# MCU.net
KiCad netlist of a schematic drawn in Altium Designer
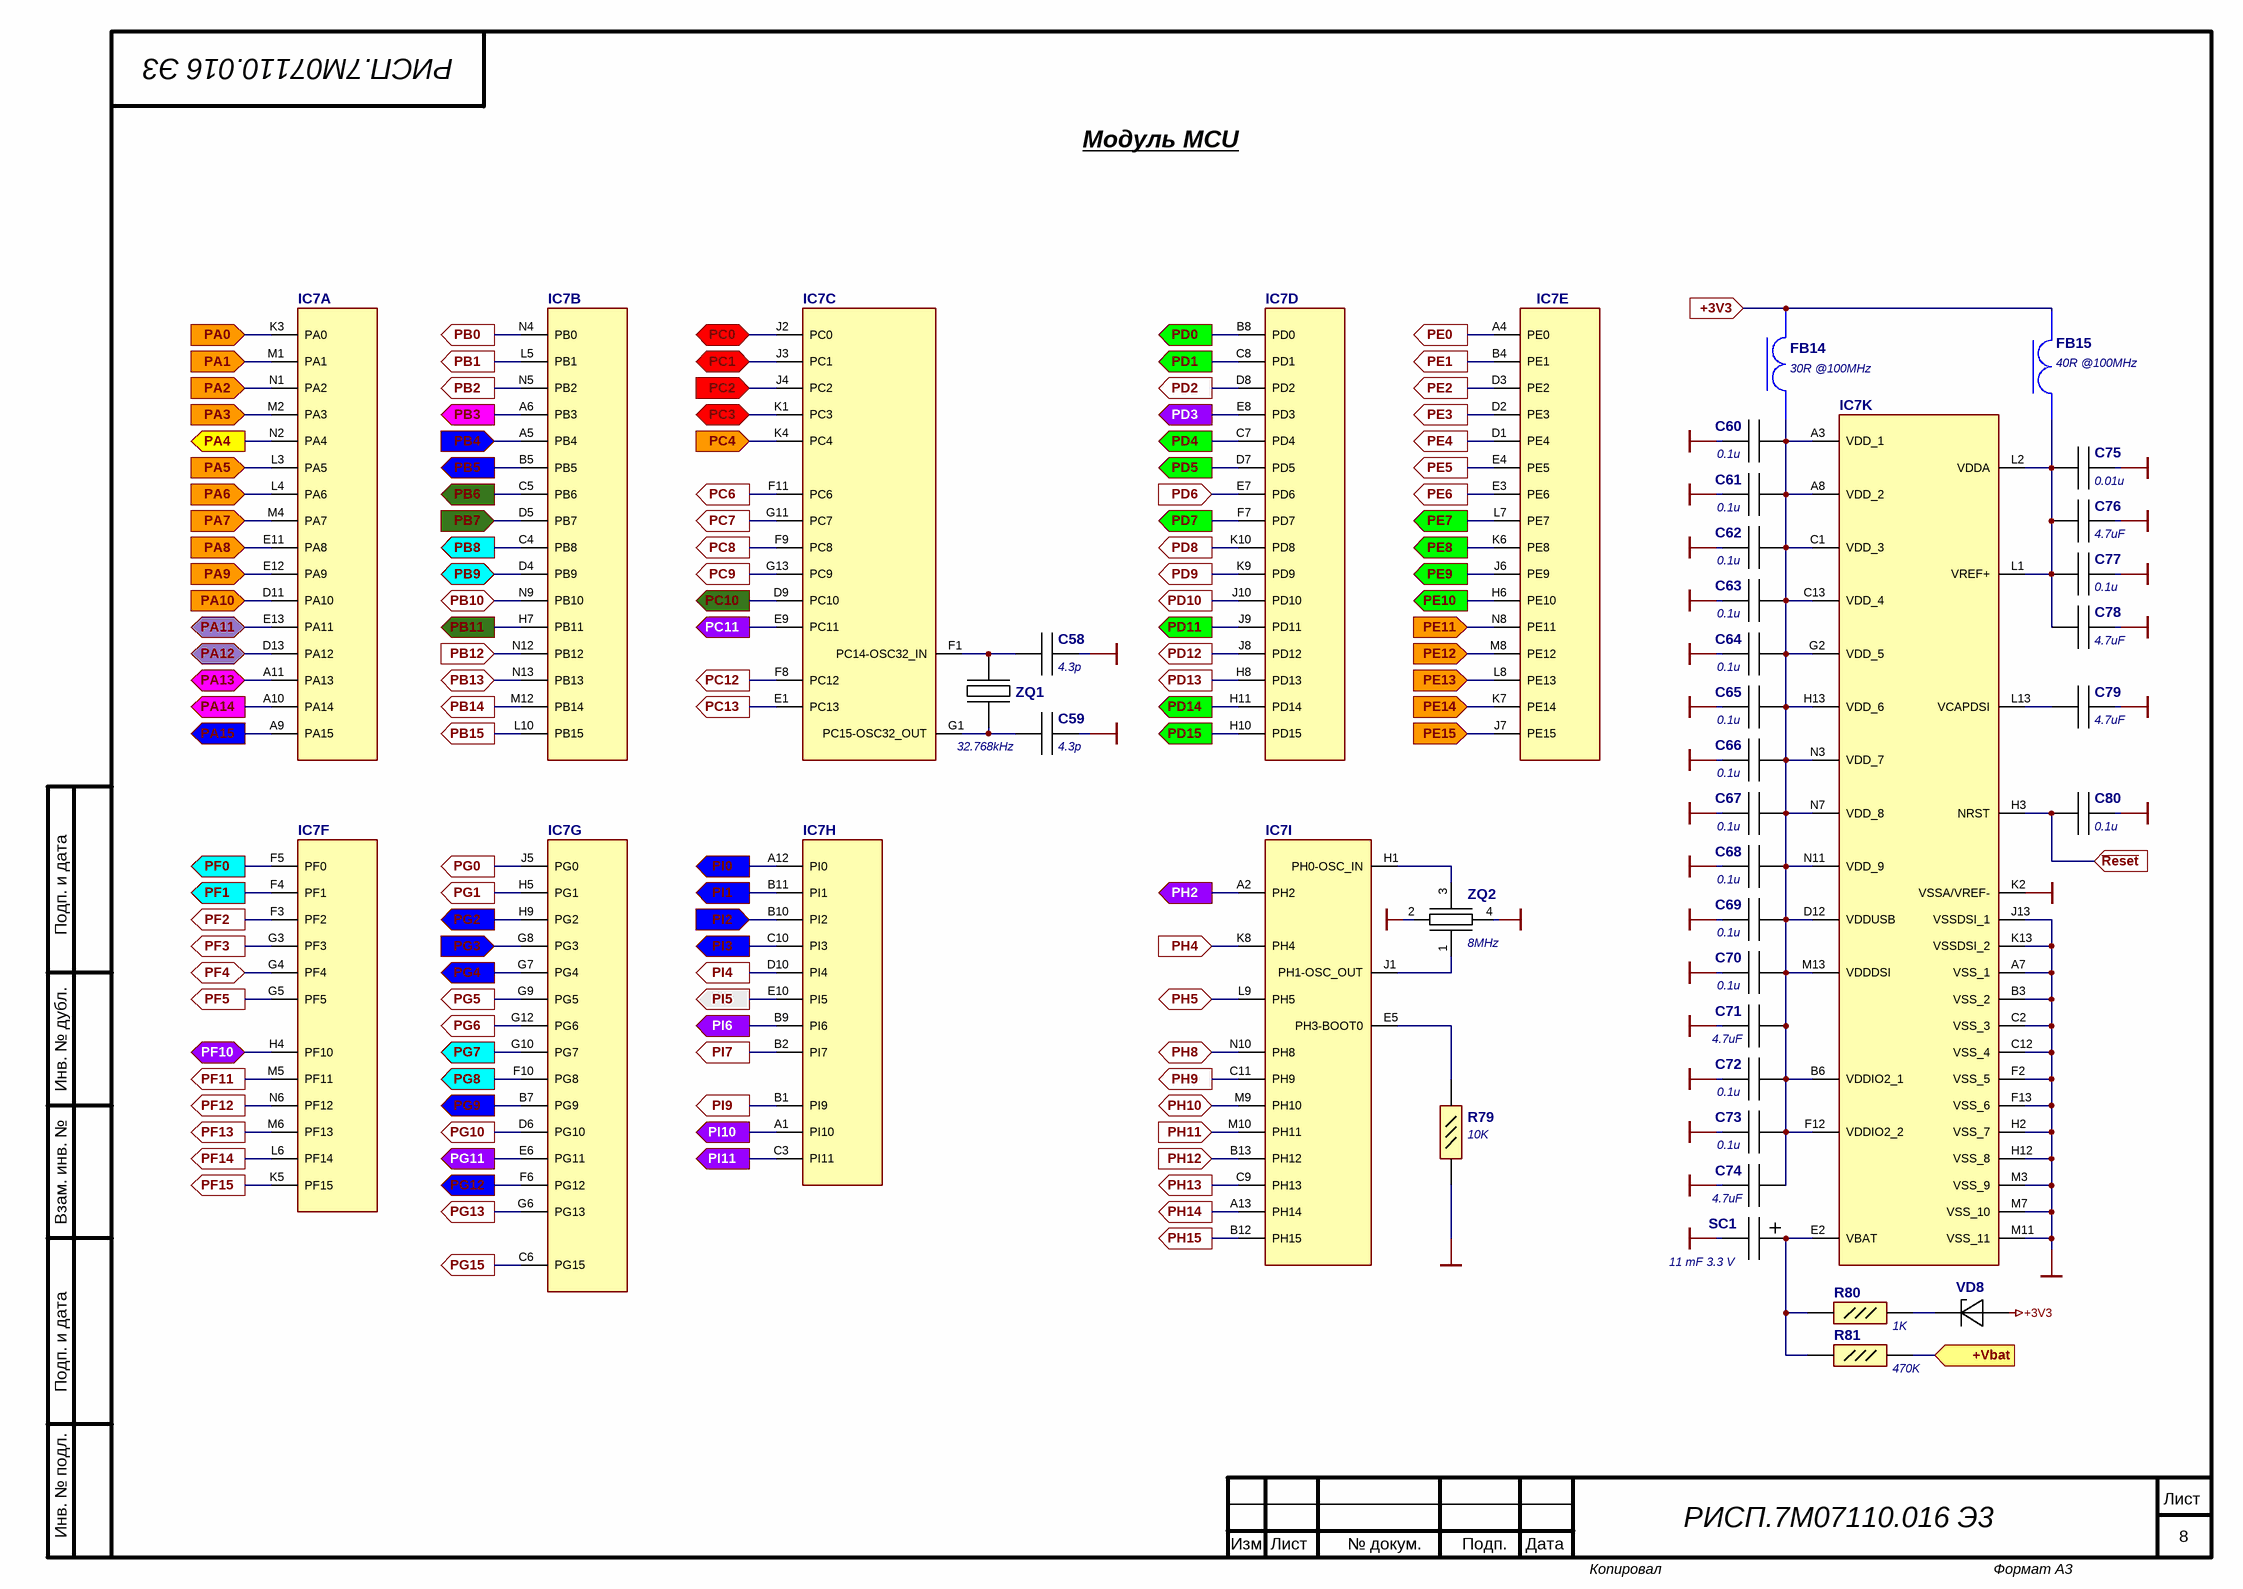
[diagram p0: Модуль MCU.SchDoc]

(export (version "E")
  (design (tool "Eeschema 10.0.6"))
  (components
    (comp (ref "C58")
      (value "4.3p")
      (footprint ":CAP0402 100x50x50")
      (description "CAP CER  50V C0G/NP0 0402")
      (fields (field (name "MANUFACTURER_PART_NUMBER") "GJM1555C1H4R3CB01D"))
      (libsource (lib "Capacitors 0402") (part "GJM1555C1H4R3CB01D"))
    )
    (comp (ref "C59")
      (value "4.3p")
      (footprint ":CAP0402 100x50x50")
      (description "CAP CER  50V C0G/NP0 0402")
      (fields (field (name "MANUFACTURER_PART_NUMBER") "GJM1555C1H4R3CB01D"))
      (libsource (lib "Capacitors 0402") (part "GJM1555C1H4R3CB01D"))
    )
    (comp (ref "C60")
      (value "0.1u")
      (footprint ":CAP0402 100x50x50")
      (description "±10% 25V Ceramic Capacitor X7R 0402 (1005 Metric)")
      (fields
        (field (name "MANUFACTURER_PART_NUMBER") "GRM155R71E104KE14J")
        (field (name "MOUSER PART NUMBER") "81-GRM155R71E104KE4J")
      )
      (libsource (lib "Capacitors 0402") (part "GRM155R71E104KE14J"))
    )
    (comp (ref "C61")
      (value "0.1u")
      (footprint ":CAP0402 100x50x50")
      (description "±10% 25V Ceramic Capacitor X7R 0402 (1005 Metric)")
      (fields
        (field (name "MANUFACTURER_PART_NUMBER") "GRM155R71E104KE14J")
        (field (name "MOUSER PART NUMBER") "81-GRM155R71E104KE4J")
      )
      (libsource (lib "Capacitors 0402") (part "GRM155R71E104KE14J"))
    )
    (comp (ref "C62")
      (value "0.1u")
      (footprint ":CAP0402 100x50x50")
      (description "±10% 25V Ceramic Capacitor X7R 0402 (1005 Metric)")
      (fields
        (field (name "MANUFACTURER_PART_NUMBER") "GRM155R71E104KE14J")
        (field (name "MOUSER PART NUMBER") "81-GRM155R71E104KE4J")
      )
      (libsource (lib "Capacitors 0402") (part "GRM155R71E104KE14J"))
    )
    (comp (ref "C63")
      (value "0.1u")
      (footprint ":CAP0402 100x50x50")
      (description "±10% 25V Ceramic Capacitor X7R 0402 (1005 Metric)")
      (fields
        (field (name "MANUFACTURER_PART_NUMBER") "GRM155R71E104KE14J")
        (field (name "MOUSER PART NUMBER") "81-GRM155R71E104KE4J")
      )
      (libsource (lib "Capacitors 0402") (part "GRM155R71E104KE14J"))
    )
    (comp (ref "C64")
      (value "0.1u")
      (footprint ":CAP0402 100x50x50")
      (description "±10% 25V Ceramic Capacitor X7R 0402 (1005 Metric)")
      (fields
        (field (name "MANUFACTURER_PART_NUMBER") "GRM155R71E104KE14J")
        (field (name "MOUSER PART NUMBER") "81-GRM155R71E104KE4J")
      )
      (libsource (lib "Capacitors 0402") (part "GRM155R71E104KE14J"))
    )
    (comp (ref "C65")
      (value "0.1u")
      (footprint ":CAP0402 100x50x50")
      (description "±10% 25V Ceramic Capacitor X7R 0402 (1005 Metric)")
      (fields
        (field (name "MANUFACTURER_PART_NUMBER") "GRM155R71E104KE14J")
        (field (name "MOUSER PART NUMBER") "81-GRM155R71E104KE4J")
      )
      (libsource (lib "Capacitors 0402") (part "GRM155R71E104KE14J"))
    )
    (comp (ref "C66")
      (value "0.1u")
      (footprint ":CAP0402 100x50x50")
      (description "±10% 25V Ceramic Capacitor X7R 0402 (1005 Metric)")
      (fields
        (field (name "MANUFACTURER_PART_NUMBER") "GRM155R71E104KE14J")
        (field (name "MOUSER PART NUMBER") "81-GRM155R71E104KE4J")
      )
      (libsource (lib "Capacitors 0402") (part "GRM155R71E104KE14J"))
    )
    (comp (ref "C67")
      (value "0.1u")
      (footprint ":CAP0402 100x50x50")
      (description "±10% 25V Ceramic Capacitor X7R 0402 (1005 Metric)")
      (fields
        (field (name "MANUFACTURER_PART_NUMBER") "GRM155R71E104KE14J")
        (field (name "MOUSER PART NUMBER") "81-GRM155R71E104KE4J")
      )
      (libsource (lib "Capacitors 0402") (part "GRM155R71E104KE14J"))
    )
    (comp (ref "C68")
      (value "0.1u")
      (footprint ":CAP0402 100x50x50")
      (description "±10% 25V Ceramic Capacitor X7R 0402 (1005 Metric)")
      (fields
        (field (name "MANUFACTURER_PART_NUMBER") "GRM155R71E104KE14J")
        (field (name "MOUSER PART NUMBER") "81-GRM155R71E104KE4J")
      )
      (libsource (lib "Capacitors 0402") (part "GRM155R71E104KE14J"))
    )
    (comp (ref "C69")
      (value "0.1u")
      (footprint ":CAP0402 100x50x50")
      (description "±10% 25V Ceramic Capacitor X7R 0402 (1005 Metric)")
      (fields
        (field (name "MANUFACTURER_PART_NUMBER") "GRM155R71E104KE14J")
        (field (name "MOUSER PART NUMBER") "81-GRM155R71E104KE4J")
      )
      (libsource (lib "Capacitors 0402") (part "GRM155R71E104KE14J"))
    )
    (comp (ref "C70")
      (value "0.1u")
      (footprint ":CAP0402 100x50x50")
      (description "±10% 25V Ceramic Capacitor X7R 0402 (1005 Metric)")
      (fields
        (field (name "MANUFACTURER_PART_NUMBER") "GRM155R71E104KE14J")
        (field (name "MOUSER PART NUMBER") "81-GRM155R71E104KE4J")
      )
      (libsource (lib "Capacitors 0402") (part "GRM155R71E104KE14J"))
    )
    (comp (ref "C71")
      (value "4.7uF")
      (footprint ":CAP0805 C2012X125")
      (description "CAP CER 4.7uF 25V X7R 0805")
      (fields (field (name "MANUFACTURER_PART_NUMBER") "GRM21BZ71E475KE15L"))
      (libsource (lib "Capacitors 0805") (part "GRM21BZ71E475KE15L"))
    )
    (comp (ref "C72")
      (value "0.1u")
      (footprint ":CAP0402 100x50x50")
      (description "±10% 25V Ceramic Capacitor X7R 0402 (1005 Metric)")
      (fields
        (field (name "MANUFACTURER_PART_NUMBER") "GRM155R71E104KE14J")
        (field (name "MOUSER PART NUMBER") "81-GRM155R71E104KE4J")
      )
      (libsource (lib "Capacitors 0402") (part "GRM155R71E104KE14J"))
    )
    (comp (ref "C73")
      (value "0.1u")
      (footprint ":CAP0402 100x50x50")
      (description "±10% 25V Ceramic Capacitor X7R 0402 (1005 Metric)")
      (fields
        (field (name "MANUFACTURER_PART_NUMBER") "GRM155R71E104KE14J")
        (field (name "MOUSER PART NUMBER") "81-GRM155R71E104KE4J")
      )
      (libsource (lib "Capacitors 0402") (part "GRM155R71E104KE14J"))
    )
    (comp (ref "C74")
      (value "4.7uF")
      (footprint ":CAP0805 C2012X125")
      (description "CAP CER 4.7uF 25V X7R 0805")
      (fields (field (name "MANUFACTURER_PART_NUMBER") "GRM21BZ71E475KE15L"))
      (libsource (lib "Capacitors 0805") (part "GRM21BZ71E475KE15L"))
    )
    (comp (ref "C75")
      (value "0.01u")
      (footprint ":CAP0402 100x50x50")
      (description "±5% 35V Ceramic Capacitor C0G, NP0 0402 (1005 Metric)")
      (fields (field (name "MANUFACTURER_PART_NUMBER") "GRM1555CYA103JE01D"))
      (libsource (lib "Capacitors 0402") (part "GRM1555CYA103JE01D"))
    )
    (comp (ref "C76")
      (value "4.7uF")
      (footprint ":CAP0805 C2012X125")
      (description "CAP CER 4.7uF 25V X7R 0805")
      (fields (field (name "MANUFACTURER_PART_NUMBER") "GRM21BZ71E475KE15L"))
      (libsource (lib "Capacitors 0805") (part "GRM21BZ71E475KE15L"))
    )
    (comp (ref "C77")
      (value "0.1u")
      (footprint ":CAP0402 100x50x50")
      (description "±10% 25V Ceramic Capacitor X7R 0402 (1005 Metric)")
      (fields
        (field (name "MANUFACTURER_PART_NUMBER") "GRM155R71E104KE14J")
        (field (name "MOUSER PART NUMBER") "81-GRM155R71E104KE4J")
      )
      (libsource (lib "Capacitors 0402") (part "GRM155R71E104KE14J"))
    )
    (comp (ref "C78")
      (value "4.7uF")
      (footprint ":CAP0805 C2012X125")
      (description "CAP CER 4.7uF 25V X7R 0805")
      (fields (field (name "MANUFACTURER_PART_NUMBER") "GRM21BZ71E475KE15L"))
      (libsource (lib "Capacitors 0805") (part "GRM21BZ71E475KE15L"))
    )
    (comp (ref "C79")
      (value "4.7uF")
      (footprint ":CAP0805 C2012X125")
      (description "CAP CER 4.7uF 25V X7R 0805")
      (fields (field (name "MANUFACTURER_PART_NUMBER") "GRM21BZ71E475KE15L"))
      (libsource (lib "Capacitors 0805") (part "GRM21BZ71E475KE15L"))
    )
    (comp (ref "C80")
      (value "0.1u")
      (footprint ":CAP0402 100x50x50")
      (description "±10% 25V Ceramic Capacitor X7R 0402 (1005 Metric)")
      (fields
        (field (name "MANUFACTURER_PART_NUMBER") "GRM155R71E104KE14J")
        (field (name "MOUSER PART NUMBER") "81-GRM155R71E104KE4J")
      )
      (libsource (lib "Capacitors 0402") (part "GRM155R71E104KE14J"))
    )
    (comp (ref "FB14")
      (value "30R @100MHz")
      (footprint ":FER BLM18SP300SN1D")
      (description "30 Ohms @ 100MHz 1 Power Line Ferrite Bead 0603 (1608 Metric) 6A 8mOhm")
      (fields
        (field (name "MANUFACTURER_PART_NUMBER") "BLM18SP300SN1D")
        (field (name "MOUSER PART NUMBER") "81-BLM18SP300SN1D")
      )
      (libsource (lib "Ferrite Bead") (part "BLM18SP300SN1D"))
    )
    (comp (ref "FB15")
      (value "40R @100MHz")
      (footprint ":FER MMZ1005Y400CTD25")
      (description "40 Ohms @ 100MHz 1 Signal Line Ferrite Bead 0402 (1005 Metric) 550mA 100mOhm")
      (fields
        (field (name "MANUFACTURER_PART_NUMBER") "MMZ1005Y400CTD25")
        (field (name "MOUSER PART NUMBER") "810-MMZ1005Y400CTD25")
      )
      (libsource (lib "Ferrite Bead") (part "MMZ1005Y400CTD25"))
    )
    (comp (ref "IC7")
      (value "STM32L4S9AII6")
      (footprint ":BGA169 P700X700X60")
      (description "MCU 32BIT 2MB FLASH")
      (fields (field (name "MOUSER PART NUMBER") "511-STM32L4S9AII6"))
      (libsource (lib "Digital ICs") (part "STM32L4S9AII6"))
    )
    (comp (ref "R79")
      (value "RC0402FR-07")
      (footprint ":RES0402")
      (fields (field (name "MANUFACTURER_PART_NUMBER (PART 2: VALUE)") "10K"))
      (libsource (lib "Resistors 0402") (part "RC0402FR-07"))
    )
    (comp (ref "R80")
      (value "RC0402FR-07")
      (footprint ":RES0402")
      (fields (field (name "MANUFACTURER_PART_NUMBER (PART 2: VALUE)") "1K"))
      (libsource (lib "") (part "RC0402FR-07_1"))
    )
    (comp (ref "R81")
      (value "RC0402FR-07")
      (footprint ":RES0402")
      (fields (field (name "MANUFACTURER_PART_NUMBER (PART 2: VALUE)") "470K"))
      (libsource (lib "") (part "RC0402FR-07_1"))
    )
    (comp (ref "SC1")
      (value "11 mF 3.3 V")
      (footprint ":CAP CPH3225A")
      (description "11 mF (EDLC) Supercapacitor 3.3 V 1210 (3225 Metric)")
      (fields
        (field (name "MANUFACTURER_PART_NUMBER") "CPH3225A")
        (field (name "MOUSER PART NUMBER") "628-CPH3225A")
      )
      (libsource (lib "Super Capacitors") (part "CPH3225A"))
    )
    (comp (ref "VD8")
      (value "30V 0.1A")
      (footprint ":DIODE SOD-923F")
      (description "Diodes Schottky 0402 30V 0.1A")
      (fields
        (field (name "MANUFACTURER_PART_NUMBER") "CDBQR0130R")
        (field (name "MOUSER PART NUMBER") "750-CDBQR0130R")
      )
      (libsource (lib "Diodes 0402") (part "CDBQR0130R"))
    )
    (comp (ref "ZQ1")
      (value "32.768kHz")
      (footprint ":RESO 12.87181")
      (description "CRYSTAL 32.7680KHZ\r\n±20ppm Crystal 12.5pF 2-SMD\r\nESR: 70 kOhms")
      (fields (field (name "MANUFACTURER_PART_NUMBER") "12.87181"))
      (libsource (lib "Crystal and TXCO") (part "12.87181"))
    )
    (comp (ref "ZQ2")
      (value "8MHz")
      (footprint ":RESO LFXTAL069277REEL")
      (description "CRYSTAL 8MHz\r\n±20ppm Crystal 20pF 4-SMD\r\nESR: 150 Ohms")
      (fields (field (name "MANUFACTURER_PART_NUMBER") "LFXTAL069277REEL"))
      (libsource (lib "Crystal and TXCO") (part "LFXTAL069277REEL"))
    )
  )
  (nets
    (net (code "1") (name "+3V3") (class "Default")
      (node (ref "FB14") (pin "2") (pinfunction "2_2") (pintype "passive"))
      (node (ref "FB15") (pin "1") (pinfunction "1_1") (pintype "passive"))
      (node (ref "VD8") (pin "2") (pinfunction "A_2") (pintype "passive"))
    )
    (net (code "2") (name "/+Vbat") (class "Default")
      (node (ref "R81") (pin "1") (pinfunction "1_1") (pintype "passive"))
    )
    (net (code "3") (name "/PA0") (class "Default")
      (node (ref "IC7") (pin "K3") (pinfunction "PA0_K3") (pintype "passive"))
    )
    (net (code "4") (name "/PA1") (class "Default")
      (node (ref "IC7") (pin "M1") (pinfunction "PA1_M1") (pintype "passive"))
    )
    (net (code "5") (name "/PA2") (class "Default")
      (node (ref "IC7") (pin "N1") (pinfunction "PA2_N1") (pintype "passive"))
    )
    (net (code "6") (name "/PA3") (class "Default")
      (node (ref "IC7") (pin "M2") (pinfunction "PA3_M2") (pintype "passive"))
    )
    (net (code "7") (name "/PA4") (class "Default")
      (node (ref "IC7") (pin "N2") (pinfunction "PA4_N2") (pintype "passive"))
    )
    (net (code "8") (name "/PA5") (class "Default")
      (node (ref "IC7") (pin "L3") (pinfunction "PA5_L3") (pintype "passive"))
    )
    (net (code "9") (name "/PA6") (class "Default")
      (node (ref "IC7") (pin "L4") (pinfunction "PA6_L4") (pintype "passive"))
    )
    (net (code "10") (name "/PA7") (class "Default")
      (node (ref "IC7") (pin "M4") (pinfunction "PA7_M4") (pintype "passive"))
    )
    (net (code "11") (name "/PA8") (class "Default")
      (node (ref "IC7") (pin "E11") (pinfunction "PA8_E11") (pintype "passive"))
    )
    (net (code "12") (name "/PA9") (class "Default")
      (node (ref "IC7") (pin "E12") (pinfunction "PA9_E12") (pintype "passive"))
    )
    (net (code "13") (name "/PA10") (class "Default")
      (node (ref "IC7") (pin "D11") (pinfunction "PA10_D11") (pintype "passive"))
    )
    (net (code "14") (name "/PA11") (class "Default")
      (node (ref "IC7") (pin "E13") (pinfunction "PA11_E13") (pintype "passive"))
    )
    (net (code "15") (name "/PA12") (class "Default")
      (node (ref "IC7") (pin "D13") (pinfunction "PA12_D13") (pintype "passive"))
    )
    (net (code "16") (name "/PA13") (class "Default")
      (node (ref "IC7") (pin "A11") (pinfunction "PA13_A11") (pintype "passive"))
    )
    (net (code "17") (name "/PA14") (class "Default")
      (node (ref "IC7") (pin "A10") (pinfunction "PA14_A10") (pintype "passive"))
    )
    (net (code "18") (name "/PA15") (class "Default")
      (node (ref "IC7") (pin "A9") (pinfunction "PA15_A9") (pintype "passive"))
    )
    (net (code "19") (name "/PB0") (class "Default")
      (node (ref "IC7") (pin "N4") (pinfunction "PB0_N4") (pintype "passive"))
    )
    (net (code "20") (name "/PB1") (class "Default")
      (node (ref "IC7") (pin "L5") (pinfunction "PB1_L5") (pintype "passive"))
    )
    (net (code "21") (name "/PB2") (class "Default")
      (node (ref "IC7") (pin "N5") (pinfunction "PB2_N5") (pintype "passive"))
    )
    (net (code "22") (name "/PB3") (class "Default")
      (node (ref "IC7") (pin "A6") (pinfunction "PB3_A6") (pintype "passive"))
    )
    (net (code "23") (name "/PB4") (class "Default")
      (node (ref "IC7") (pin "A5") (pinfunction "PB4_A5") (pintype "passive"))
    )
    (net (code "24") (name "/PB5") (class "Default")
      (node (ref "IC7") (pin "B5") (pinfunction "PB5_B5") (pintype "passive"))
    )
    (net (code "25") (name "/PB6") (class "Default")
      (node (ref "IC7") (pin "C5") (pinfunction "PB6_C5") (pintype "passive"))
    )
    (net (code "26") (name "/PB7") (class "Default")
      (node (ref "IC7") (pin "D5") (pinfunction "PB7_D5") (pintype "passive"))
    )
    (net (code "27") (name "/PB8") (class "Default")
      (node (ref "IC7") (pin "C4") (pinfunction "PB8_C4") (pintype "passive"))
    )
    (net (code "28") (name "/PB9") (class "Default")
      (node (ref "IC7") (pin "D4") (pinfunction "PB9_D4") (pintype "passive"))
    )
    (net (code "29") (name "/PB10") (class "Default")
      (node (ref "IC7") (pin "N9") (pinfunction "PB10_N9") (pintype "passive"))
    )
    (net (code "30") (name "/PB11") (class "Default")
      (node (ref "IC7") (pin "H7") (pinfunction "PB11_H7") (pintype "passive"))
    )
    (net (code "31") (name "/PB12") (class "Default")
      (node (ref "IC7") (pin "N12") (pinfunction "PB12_N12") (pintype "passive"))
    )
    (net (code "32") (name "/PB13") (class "Default")
      (node (ref "IC7") (pin "N13") (pinfunction "PB13_N13") (pintype "passive"))
    )
    (net (code "33") (name "/PB14") (class "Default")
      (node (ref "IC7") (pin "M12") (pinfunction "PB14_M12") (pintype "passive"))
    )
    (net (code "34") (name "/PB15") (class "Default")
      (node (ref "IC7") (pin "L10") (pinfunction "PB15_L10") (pintype "passive"))
    )
    (net (code "35") (name "/PC0") (class "Default")
      (node (ref "IC7") (pin "J2") (pinfunction "PC0_J2") (pintype "passive"))
    )
    (net (code "36") (name "/PC1") (class "Default")
      (node (ref "IC7") (pin "J3") (pinfunction "PC1_J3") (pintype "passive"))
    )
    (net (code "37") (name "/PC2") (class "Default")
      (node (ref "IC7") (pin "J4") (pinfunction "PC2_J4") (pintype "passive"))
    )
    (net (code "38") (name "/PC3") (class "Default")
      (node (ref "IC7") (pin "K1") (pinfunction "PC3_K1") (pintype "passive"))
    )
    (net (code "39") (name "/PC4") (class "Default")
      (node (ref "IC7") (pin "K4") (pinfunction "PC4_K4") (pintype "passive"))
    )
    (net (code "40") (name "/PC6") (class "Default")
      (node (ref "IC7") (pin "F11") (pinfunction "PC6_F11") (pintype "passive"))
    )
    (net (code "41") (name "/PC7") (class "Default")
      (node (ref "IC7") (pin "G11") (pinfunction "PC7_G11") (pintype "passive"))
    )
    (net (code "42") (name "/PC8") (class "Default")
      (node (ref "IC7") (pin "F9") (pinfunction "PC8_F9") (pintype "passive"))
    )
    (net (code "43") (name "/PC9") (class "Default")
      (node (ref "IC7") (pin "G13") (pinfunction "PC9_G13") (pintype "passive"))
    )
    (net (code "44") (name "/PC10") (class "Default")
      (node (ref "IC7") (pin "D9") (pinfunction "PC10_D9") (pintype "passive"))
    )
    (net (code "45") (name "/PC11") (class "Default")
      (node (ref "IC7") (pin "E9") (pinfunction "PC11_E9") (pintype "passive"))
    )
    (net (code "46") (name "/PC12") (class "Default")
      (node (ref "IC7") (pin "F8") (pinfunction "PC12_F8") (pintype "passive"))
    )
    (net (code "47") (name "/PC13") (class "Default")
      (node (ref "IC7") (pin "E1") (pinfunction "PC13_E1") (pintype "passive"))
    )
    (net (code "48") (name "/PD0") (class "Default")
      (node (ref "IC7") (pin "B8") (pinfunction "PD0_B8") (pintype "passive"))
    )
    (net (code "49") (name "/PD1") (class "Default")
      (node (ref "IC7") (pin "C8") (pinfunction "PD1_C8") (pintype "passive"))
    )
    (net (code "50") (name "/PD2") (class "Default")
      (node (ref "IC7") (pin "D8") (pinfunction "PD2_D8") (pintype "passive"))
    )
    (net (code "51") (name "/PD3") (class "Default")
      (node (ref "IC7") (pin "E8") (pinfunction "PD3_E8") (pintype "passive"))
    )
    (net (code "52") (name "/PD4") (class "Default")
      (node (ref "IC7") (pin "C7") (pinfunction "PD4_C7") (pintype "passive"))
    )
    (net (code "53") (name "/PD5") (class "Default")
      (node (ref "IC7") (pin "D7") (pinfunction "PD5_D7") (pintype "passive"))
    )
    (net (code "54") (name "/PD6") (class "Default")
      (node (ref "IC7") (pin "E7") (pinfunction "PD6_E7") (pintype "passive"))
    )
    (net (code "55") (name "/PD7") (class "Default")
      (node (ref "IC7") (pin "F7") (pinfunction "PD7_F7") (pintype "passive"))
    )
    (net (code "56") (name "/PD8") (class "Default")
      (node (ref "IC7") (pin "K10") (pinfunction "PD8_K10") (pintype "passive"))
    )
    (net (code "57") (name "/PD9") (class "Default")
      (node (ref "IC7") (pin "K9") (pinfunction "PD9_K9") (pintype "passive"))
    )
    (net (code "58") (name "/PD10") (class "Default")
      (node (ref "IC7") (pin "J10") (pinfunction "PD10_J10") (pintype "passive"))
    )
    (net (code "59") (name "/PD11") (class "Default")
      (node (ref "IC7") (pin "J9") (pinfunction "PD11_J9") (pintype "passive"))
    )
    (net (code "60") (name "/PD12") (class "Default")
      (node (ref "IC7") (pin "J8") (pinfunction "PD12_J8") (pintype "passive"))
    )
    (net (code "61") (name "/PD13") (class "Default")
      (node (ref "IC7") (pin "H8") (pinfunction "PD13_H8") (pintype "passive"))
    )
    (net (code "62") (name "/PD14") (class "Default")
      (node (ref "IC7") (pin "H11") (pinfunction "PD14_H11") (pintype "passive"))
    )
    (net (code "63") (name "/PD15") (class "Default")
      (node (ref "IC7") (pin "H10") (pinfunction "PD15_H10") (pintype "passive"))
    )
    (net (code "64") (name "/PE0") (class "Default")
      (node (ref "IC7") (pin "A4") (pinfunction "PE0_A4") (pintype "passive"))
    )
    (net (code "65") (name "/PE1") (class "Default")
      (node (ref "IC7") (pin "B4") (pinfunction "PE1_B4") (pintype "passive"))
    )
    (net (code "66") (name "/PE2") (class "Default")
      (node (ref "IC7") (pin "D3") (pinfunction "PE2_D3") (pintype "passive"))
    )
    (net (code "67") (name "/PE3") (class "Default")
      (node (ref "IC7") (pin "D2") (pinfunction "PE3_D2") (pintype "passive"))
    )
    (net (code "68") (name "/PE4") (class "Default")
      (node (ref "IC7") (pin "D1") (pinfunction "PE4_D1") (pintype "passive"))
    )
    (net (code "69") (name "/PE5") (class "Default")
      (node (ref "IC7") (pin "E4") (pinfunction "PE5_E4") (pintype "passive"))
    )
    (net (code "70") (name "/PE6") (class "Default")
      (node (ref "IC7") (pin "E3") (pinfunction "PE6_E3") (pintype "passive"))
    )
    (net (code "71") (name "/PE7") (class "Default")
      (node (ref "IC7") (pin "L7") (pinfunction "PE7_L7") (pintype "passive"))
    )
    (net (code "72") (name "/PE8") (class "Default")
      (node (ref "IC7") (pin "K6") (pinfunction "PE8_K6") (pintype "passive"))
    )
    (net (code "73") (name "/PE9") (class "Default")
      (node (ref "IC7") (pin "J6") (pinfunction "PE9_J6") (pintype "passive"))
    )
    (net (code "74") (name "/PE10") (class "Default")
      (node (ref "IC7") (pin "H6") (pinfunction "PE10_H6") (pintype "passive"))
    )
    (net (code "75") (name "/PE11") (class "Default")
      (node (ref "IC7") (pin "N8") (pinfunction "PE11_N8") (pintype "passive"))
    )
    (net (code "76") (name "/PE12") (class "Default")
      (node (ref "IC7") (pin "M8") (pinfunction "PE12_M8") (pintype "passive"))
    )
    (net (code "77") (name "/PE13") (class "Default")
      (node (ref "IC7") (pin "L8") (pinfunction "PE13_L8") (pintype "passive"))
    )
    (net (code "78") (name "/PE14") (class "Default")
      (node (ref "IC7") (pin "K7") (pinfunction "PE14_K7") (pintype "passive"))
    )
    (net (code "79") (name "/PE15") (class "Default")
      (node (ref "IC7") (pin "J7") (pinfunction "PE15_J7") (pintype "passive"))
    )
    (net (code "80") (name "/PF0") (class "Default")
      (node (ref "IC7") (pin "F5") (pinfunction "PF0_F5") (pintype "passive"))
    )
    (net (code "81") (name "/PF1") (class "Default")
      (node (ref "IC7") (pin "F4") (pinfunction "PF1_F4") (pintype "passive"))
    )
    (net (code "82") (name "/PF2") (class "Default")
      (node (ref "IC7") (pin "F3") (pinfunction "PF2_F3") (pintype "passive"))
    )
    (net (code "83") (name "/PF3") (class "Default")
      (node (ref "IC7") (pin "G3") (pinfunction "PF3_G3") (pintype "passive"))
    )
    (net (code "84") (name "/PF4") (class "Default")
      (node (ref "IC7") (pin "G4") (pinfunction "PF4_G4") (pintype "passive"))
    )
    (net (code "85") (name "/PF5") (class "Default")
      (node (ref "IC7") (pin "G5") (pinfunction "PF5_G5") (pintype "passive"))
    )
    (net (code "86") (name "/PF10") (class "Default")
      (node (ref "IC7") (pin "H4") (pinfunction "PF10_H4") (pintype "passive"))
    )
    (net (code "87") (name "/PF11") (class "Default")
      (node (ref "IC7") (pin "M5") (pinfunction "PF11_M5") (pintype "passive"))
    )
    (net (code "88") (name "/PF12") (class "Default")
      (node (ref "IC7") (pin "N6") (pinfunction "PF12_N6") (pintype "passive"))
    )
    (net (code "89") (name "/PF13") (class "Default")
      (node (ref "IC7") (pin "M6") (pinfunction "PF13_M6") (pintype "passive"))
    )
    (net (code "90") (name "/PF14") (class "Default")
      (node (ref "IC7") (pin "L6") (pinfunction "PF14_L6") (pintype "passive"))
    )
    (net (code "91") (name "/PF15") (class "Default")
      (node (ref "IC7") (pin "K5") (pinfunction "PF15_K5") (pintype "passive"))
    )
    (net (code "92") (name "/PG0") (class "Default")
      (node (ref "IC7") (pin "J5") (pinfunction "PG0_J5") (pintype "passive"))
    )
    (net (code "93") (name "/PG1") (class "Default")
      (node (ref "IC7") (pin "H5") (pinfunction "PG1_H5") (pintype "passive"))
    )
    (net (code "94") (name "/PG2") (class "Default")
      (node (ref "IC7") (pin "H9") (pinfunction "PG2_H9") (pintype "passive"))
    )
    (net (code "95") (name "/PG3") (class "Default")
      (node (ref "IC7") (pin "G8") (pinfunction "PG3_G8") (pintype "passive"))
    )
    (net (code "96") (name "/PG4") (class "Default")
      (node (ref "IC7") (pin "G7") (pinfunction "PG4_G7") (pintype "passive"))
    )
    (net (code "97") (name "/PG5") (class "Default")
      (node (ref "IC7") (pin "G9") (pinfunction "PG5_G9") (pintype "passive"))
    )
    (net (code "98") (name "/PG6") (class "Default")
      (node (ref "IC7") (pin "G12") (pinfunction "PG6_G12") (pintype "passive"))
    )
    (net (code "99") (name "/PG7") (class "Default")
      (node (ref "IC7") (pin "G10") (pinfunction "PG7_G10") (pintype "passive"))
    )
    (net (code "100") (name "/PG8") (class "Default")
      (node (ref "IC7") (pin "F10") (pinfunction "PG8_F10") (pintype "passive"))
    )
    (net (code "101") (name "/PG9") (class "Default")
      (node (ref "IC7") (pin "B7") (pinfunction "PG9_B7") (pintype "passive"))
    )
    (net (code "102") (name "/PG10") (class "Default")
      (node (ref "IC7") (pin "D6") (pinfunction "PG10_D6") (pintype "passive"))
    )
    (net (code "103") (name "/PG11") (class "Default")
      (node (ref "IC7") (pin "E6") (pinfunction "PG11_E6") (pintype "passive"))
    )
    (net (code "104") (name "/PG12") (class "Default")
      (node (ref "IC7") (pin "F6") (pinfunction "PG12_F6") (pintype "passive"))
    )
    (net (code "105") (name "/PG13") (class "Default")
      (node (ref "IC7") (pin "G6") (pinfunction "PG13_G6") (pintype "passive"))
    )
    (net (code "106") (name "/PG15") (class "Default")
      (node (ref "IC7") (pin "C6") (pinfunction "PG15_C6") (pintype "passive"))
    )
    (net (code "107") (name "/PH2") (class "Default")
      (node (ref "IC7") (pin "A2") (pinfunction "PH2_A2") (pintype "passive"))
    )
    (net (code "108") (name "/PH4") (class "Default")
      (node (ref "IC7") (pin "K8") (pinfunction "PH4_K8") (pintype "passive"))
    )
    (net (code "109") (name "/PH5") (class "Default")
      (node (ref "IC7") (pin "L9") (pinfunction "PH5_L9") (pintype "passive"))
    )
    (net (code "110") (name "/PH8") (class "Default")
      (node (ref "IC7") (pin "N10") (pinfunction "PH8_N10") (pintype "passive"))
    )
    (net (code "111") (name "/PH9") (class "Default")
      (node (ref "IC7") (pin "C11") (pinfunction "PH9_C11") (pintype "passive"))
    )
    (net (code "112") (name "/PH10") (class "Default")
      (node (ref "IC7") (pin "M9") (pinfunction "PH10_M9") (pintype "passive"))
    )
    (net (code "113") (name "/PH11") (class "Default")
      (node (ref "IC7") (pin "M10") (pinfunction "PH11_M10") (pintype "passive"))
    )
    (net (code "114") (name "/PH12") (class "Default")
      (node (ref "IC7") (pin "B13") (pinfunction "PH12_B13") (pintype "passive"))
    )
    (net (code "115") (name "/PH13") (class "Default")
      (node (ref "IC7") (pin "C9") (pinfunction "PH13_C9") (pintype "passive"))
    )
    (net (code "116") (name "/PH14") (class "Default")
      (node (ref "IC7") (pin "A13") (pinfunction "PH14_A13") (pintype "passive"))
    )
    (net (code "117") (name "/PH15") (class "Default")
      (node (ref "IC7") (pin "B12") (pinfunction "PH15_B12") (pintype "passive"))
    )
    (net (code "118") (name "/PI0") (class "Default")
      (node (ref "IC7") (pin "A12") (pinfunction "PI0_A12") (pintype "passive"))
    )
    (net (code "119") (name "/PI1") (class "Default")
      (node (ref "IC7") (pin "B11") (pinfunction "PI1_B11") (pintype "passive"))
    )
    (net (code "120") (name "/PI2") (class "Default")
      (node (ref "IC7") (pin "B10") (pinfunction "PI2_B10") (pintype "passive"))
    )
    (net (code "121") (name "/PI3") (class "Default")
      (node (ref "IC7") (pin "C10") (pinfunction "PI3_C10") (pintype "passive"))
    )
    (net (code "122") (name "/PI4") (class "Default")
      (node (ref "IC7") (pin "D10") (pinfunction "PI4_D10") (pintype "passive"))
    )
    (net (code "123") (name "/PI5") (class "Default")
      (node (ref "IC7") (pin "E10") (pinfunction "PI5_E10") (pintype "passive"))
    )
    (net (code "124") (name "/PI6") (class "Default")
      (node (ref "IC7") (pin "B9") (pinfunction "PI6_B9") (pintype "passive"))
    )
    (net (code "125") (name "/PI7") (class "Default")
      (node (ref "IC7") (pin "B2") (pinfunction "PI7_B2") (pintype "passive"))
    )
    (net (code "126") (name "/PI9") (class "Default")
      (node (ref "IC7") (pin "B1") (pinfunction "PI9_B1") (pintype "passive"))
    )
    (net (code "127") (name "/PI10") (class "Default")
      (node (ref "IC7") (pin "A1") (pinfunction "PI10_A1") (pintype "passive"))
    )
    (net (code "128") (name "/PI11") (class "Default")
      (node (ref "IC7") (pin "C3") (pinfunction "PI11_C3") (pintype "passive"))
    )
    (net (code "129") (name "/~{Reset}") (class "Default")
      (node (ref "C80") (pin "1") (pinfunction "1_1") (pintype "passive"))
      (node (ref "IC7") (pin "H3") (pinfunction "NRST_H3") (pintype "passive"))
    )
    (net (code "130") (name "GND") (class "Default")
      (node (ref "C58") (pin "2") (pinfunction "2_2") (pintype "passive"))
      (node (ref "C59") (pin "2") (pinfunction "2_2") (pintype "passive"))
      (node (ref "C60") (pin "1") (pinfunction "1_1") (pintype "passive"))
      (node (ref "C61") (pin "1") (pinfunction "1_1") (pintype "passive"))
      (node (ref "C62") (pin "1") (pinfunction "1_1") (pintype "passive"))
      (node (ref "C63") (pin "1") (pinfunction "1_1") (pintype "passive"))
      (node (ref "C64") (pin "1") (pinfunction "1_1") (pintype "passive"))
      (node (ref "C65") (pin "1") (pinfunction "1_1") (pintype "passive"))
      (node (ref "C66") (pin "1") (pinfunction "1_1") (pintype "passive"))
      (node (ref "C67") (pin "1") (pinfunction "1_1") (pintype "passive"))
      (node (ref "C68") (pin "1") (pinfunction "1_1") (pintype "passive"))
      (node (ref "C69") (pin "1") (pinfunction "1_1") (pintype "passive"))
      (node (ref "C70") (pin "1") (pinfunction "1_1") (pintype "passive"))
      (node (ref "C71") (pin "2") (pinfunction "2_2") (pintype "passive"))
      (node (ref "C72") (pin "1") (pinfunction "1_1") (pintype "passive"))
      (node (ref "C73") (pin "1") (pinfunction "1_1") (pintype "passive"))
      (node (ref "C74") (pin "2") (pinfunction "2_2") (pintype "passive"))
      (node (ref "C75") (pin "2") (pinfunction "2_2") (pintype "passive"))
      (node (ref "C76") (pin "2") (pinfunction "2_2") (pintype "passive"))
      (node (ref "C77") (pin "2") (pinfunction "2_2") (pintype "passive"))
      (node (ref "C78") (pin "2") (pinfunction "2_2") (pintype "passive"))
      (node (ref "C79") (pin "2") (pinfunction "2_2") (pintype "passive"))
      (node (ref "C80") (pin "2") (pinfunction "2_2") (pintype "passive"))
      (node (ref "IC7") (pin "A7") (pinfunction "VSS_1_A7") (pintype "passive"))
      (node (ref "IC7") (pin "B3") (pinfunction "VSS_2_B3") (pintype "passive"))
      (node (ref "IC7") (pin "C12") (pinfunction "VSS_4_C12") (pintype "passive"))
      (node (ref "IC7") (pin "C2") (pinfunction "VSS_3_C2") (pintype "passive"))
      (node (ref "IC7") (pin "F13") (pinfunction "VSS_6_F13") (pintype "passive"))
      (node (ref "IC7") (pin "F2") (pinfunction "VSS_5_F2") (pintype "passive"))
      (node (ref "IC7") (pin "H12") (pinfunction "VSS_8_H12") (pintype "passive"))
      (node (ref "IC7") (pin "H2") (pinfunction "VSS_7_H2") (pintype "passive"))
      (node (ref "IC7") (pin "J13") (pinfunction "VSSDSI_1_J13") (pintype "passive"))
      (node (ref "IC7") (pin "K13") (pinfunction "VSSDSI_2_K13") (pintype "passive"))
      (node (ref "IC7") (pin "K2") (pinfunction "VSSA/VREF-_K2") (pintype "passive"))
      (node (ref "IC7") (pin "M11") (pinfunction "VSS_11_M11") (pintype "passive"))
      (node (ref "IC7") (pin "M3") (pinfunction "VSS_9_M3") (pintype "passive"))
      (node (ref "IC7") (pin "M7") (pinfunction "VSS_10_M7") (pintype "passive"))
      (node (ref "R79") (pin "1") (pinfunction "1_1") (pintype "passive"))
      (node (ref "SC1") (pin "2") (pinfunction "-_2") (pintype "passive"))
      (node (ref "ZQ2") (pin "2") (pinfunction "2_2") (pintype "passive"))
      (node (ref "ZQ2") (pin "4") (pinfunction "4_4") (pintype "passive"))
    )
    (net (code "131") (name "Net-(IC7C-PC14-OSC32_IN)") (class "Default")
      (node (ref "C58") (pin "1") (pinfunction "1_1") (pintype "passive"))
      (node (ref "IC7") (pin "F1") (pinfunction "PC14-OSC32_IN_F1") (pintype "passive"))
      (node (ref "ZQ1") (pin "2") (pinfunction "2_2") (pintype "passive"))
    )
    (net (code "132") (name "Net-(IC7C-PC15-OSC32_OUT)") (class "Default")
      (node (ref "C59") (pin "1") (pinfunction "1_1") (pintype "passive"))
      (node (ref "IC7") (pin "G1") (pinfunction "PC15-OSC32_OUT_G1") (pintype "passive"))
      (node (ref "ZQ1") (pin "1") (pinfunction "1_1") (pintype "passive"))
    )
    (net (code "133") (name "Net-(IC7I-PH0-OSC_IN)") (class "Default")
      (node (ref "IC7") (pin "H1") (pinfunction "PH0-OSC_IN_H1") (pintype "passive"))
      (node (ref "ZQ2") (pin "3") (pinfunction "3_3") (pintype "passive"))
    )
    (net (code "134") (name "Net-(IC7I-PH1-OSC_OUT)") (class "Default")
      (node (ref "IC7") (pin "J1") (pinfunction "PH1-OSC_OUT_J1") (pintype "passive"))
      (node (ref "ZQ2") (pin "1") (pinfunction "1_1") (pintype "passive"))
    )
    (net (code "135") (name "Net-(IC7I-PH3-BOOT0)") (class "Default")
      (node (ref "IC7") (pin "E5") (pinfunction "PH3-BOOT0_E5") (pintype "passive"))
      (node (ref "R79") (pin "2") (pinfunction "2_2") (pintype "passive"))
    )
    (net (code "136") (name "Net-(IC7K-VBAT)") (class "Default")
      (node (ref "IC7") (pin "E2") (pinfunction "VBAT_E2") (pintype "passive"))
      (node (ref "R80") (pin "2") (pinfunction "2_2") (pintype "passive"))
      (node (ref "R81") (pin "2") (pinfunction "2_2") (pintype "passive"))
      (node (ref "SC1") (pin "1") (pinfunction "+_1") (pintype "passive"))
    )
    (net (code "137") (name "Net-(IC7K-VCAPDSI)") (class "Default")
      (node (ref "C79") (pin "1") (pinfunction "1_1") (pintype "passive"))
      (node (ref "IC7") (pin "L13") (pinfunction "VCAPDSI_L13") (pintype "passive"))
    )
    (net (code "138") (name "Net-(IC7K-VDDA)") (class "Default")
      (node (ref "C75") (pin "1") (pinfunction "1_1") (pintype "passive"))
      (node (ref "C76") (pin "1") (pinfunction "1_1") (pintype "passive"))
      (node (ref "C77") (pin "1") (pinfunction "1_1") (pintype "passive"))
      (node (ref "C78") (pin "1") (pinfunction "1_1") (pintype "passive"))
      (node (ref "FB15") (pin "2") (pinfunction "2_2") (pintype "passive"))
      (node (ref "IC7") (pin "L1") (pinfunction "VREF+_L1") (pintype "passive"))
      (node (ref "IC7") (pin "L2") (pinfunction "VDDA_L2") (pintype "passive"))
    )
    (net (code "139") (name "Net-(IC7K-VDDDSI)") (class "Default")
      (node (ref "C60") (pin "2") (pinfunction "2_2") (pintype "passive"))
      (node (ref "C61") (pin "2") (pinfunction "2_2") (pintype "passive"))
      (node (ref "C62") (pin "2") (pinfunction "2_2") (pintype "passive"))
      (node (ref "C63") (pin "2") (pinfunction "2_2") (pintype "passive"))
      (node (ref "C64") (pin "2") (pinfunction "2_2") (pintype "passive"))
      (node (ref "C65") (pin "2") (pinfunction "2_2") (pintype "passive"))
      (node (ref "C66") (pin "2") (pinfunction "2_2") (pintype "passive"))
      (node (ref "C67") (pin "2") (pinfunction "2_2") (pintype "passive"))
      (node (ref "C68") (pin "2") (pinfunction "2_2") (pintype "passive"))
      (node (ref "C69") (pin "2") (pinfunction "2_2") (pintype "passive"))
      (node (ref "C70") (pin "2") (pinfunction "2_2") (pintype "passive"))
      (node (ref "C71") (pin "1") (pinfunction "1_1") (pintype "passive"))
      (node (ref "C72") (pin "2") (pinfunction "2_2") (pintype "passive"))
      (node (ref "C73") (pin "2") (pinfunction "2_2") (pintype "passive"))
      (node (ref "C74") (pin "1") (pinfunction "1_1") (pintype "passive"))
      (node (ref "FB14") (pin "1") (pinfunction "1_1") (pintype "passive"))
      (node (ref "IC7") (pin "A3") (pinfunction "VDD_1_A3") (pintype "passive"))
      (node (ref "IC7") (pin "A8") (pinfunction "VDD_2_A8") (pintype "passive"))
      (node (ref "IC7") (pin "B6") (pinfunction "VDDIO2_1_B6") (pintype "passive"))
      (node (ref "IC7") (pin "C1") (pinfunction "VDD_3_C1") (pintype "passive"))
      (node (ref "IC7") (pin "C13") (pinfunction "VDD_4_C13") (pintype "passive"))
      (node (ref "IC7") (pin "D12") (pinfunction "VDDUSB_D12") (pintype "passive"))
      (node (ref "IC7") (pin "F12") (pinfunction "VDDIO2_2_F12") (pintype "passive"))
      (node (ref "IC7") (pin "G2") (pinfunction "VDD_5_G2") (pintype "passive"))
      (node (ref "IC7") (pin "H13") (pinfunction "VDD_6_H13") (pintype "passive"))
      (node (ref "IC7") (pin "M13") (pinfunction "VDDDSI_M13") (pintype "passive"))
      (node (ref "IC7") (pin "N11") (pinfunction "VDD_9_N11") (pintype "passive"))
      (node (ref "IC7") (pin "N3") (pinfunction "VDD_7_N3") (pintype "passive"))
      (node (ref "IC7") (pin "N7") (pinfunction "VDD_8_N7") (pintype "passive"))
    )
    (net (code "140") (name "Net-(VD8-K)") (class "Default")
      (node (ref "R80") (pin "1") (pinfunction "1_1") (pintype "passive"))
      (node (ref "VD8") (pin "1") (pinfunction "K_1") (pintype "passive"))
    )
  )
)
